# xv11_nucleo_shield.net
KiCad netlist of a schematic drawn in EAGLE
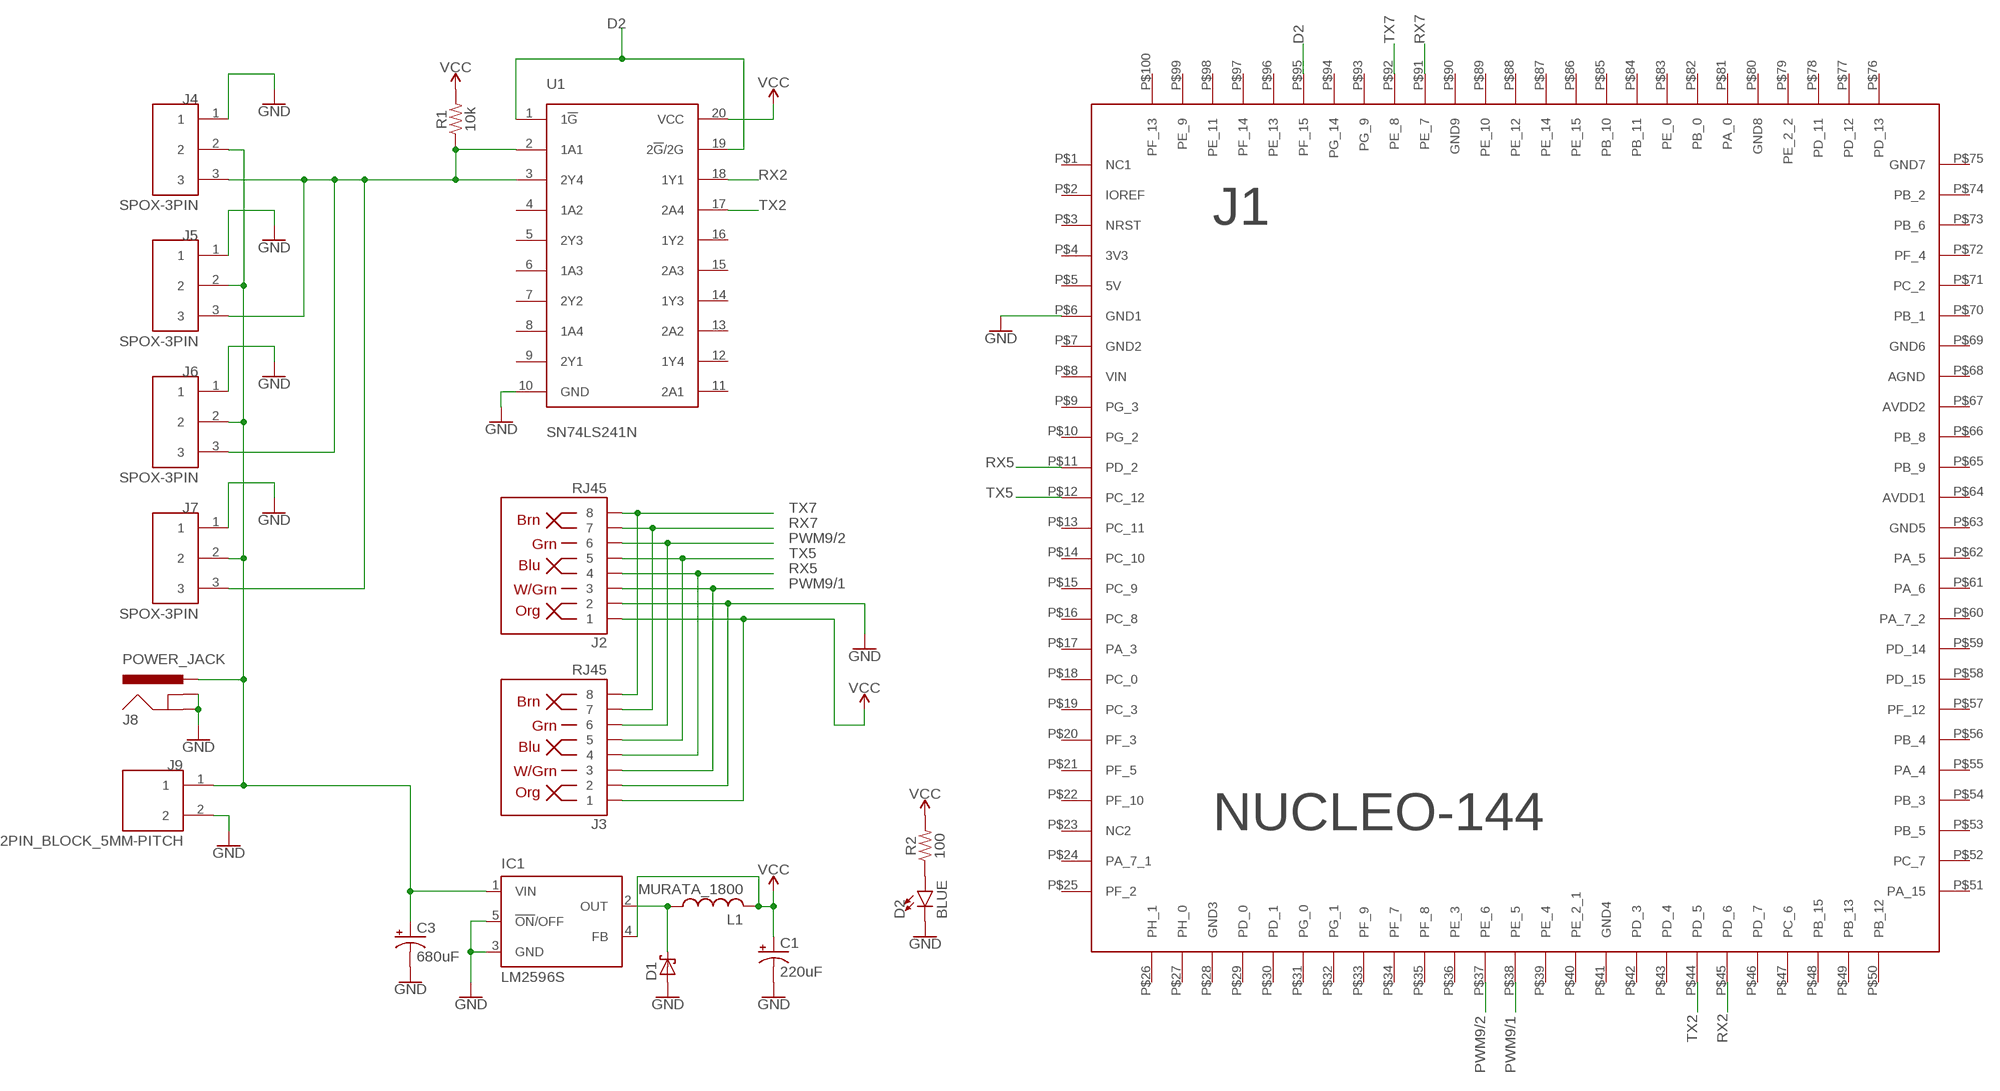
[diagram p0: schematic, sheet 1]

(export (version "E")
  (design (tool "Eeschema 10.0.6"))
  (components
    (comp (ref "C1")
      (value "220uF")
      (footprint "eagle-import:CPOL-RADIAL-2.5MM-6.5MM")
      (libsource (lib "eagle-import") (part "100UF-POLAR-RADIAL-2.5MM-25V-20%"))
    )
    (comp (ref "C3")
      (value "680uF")
      (footprint "eagle-import:EEU-FR1C681L")
      (libsource (lib "eagle-import") (part "EEU-FR1C681L"))
    )
    (comp (ref "D1")
      (value "SCHOTTKY-DIODEDO201T15")
      (footprint "eagle-import:DO201T15")
      (libsource (lib "eagle-import") (part "SCHOTTKY-DIODEDO201T15"))
    )
    (comp (ref "D2")
      (value "BLUE")
      (footprint "eagle-import:LED-1206")
      (libsource (lib "eagle-import") (part "LED-BLUE1206"))
    )
    (comp (ref "IC1")
      (value "LM2596S")
      (footprint "eagle-import:TO263-5")
      (fields (field (name "MF") "NATIONAL SEMICONDUCTOR") (field (name "MPN") "LM2596S-ADJ/NOPB"))
      (libsource (lib "eagle-import") (part "LM2596S"))
    )
    (comp (ref "J1")
      (value "NUCLEO-144")
      (footprint "eagle-import:NUCLEO-144")
      (libsource (lib "eagle-import") (part "NUCLEO-144"))
    )
    (comp (ref "J2")
      (value "RJ45")
      (footprint "eagle-import:RJ45-8")
      (libsource (lib "eagle-import") (part "RJ45-8"))
    )
    (comp (ref "J3")
      (value "RJ45")
      (footprint "eagle-import:RJ45-8")
      (libsource (lib "eagle-import") (part "RJ45-8"))
    )
    (comp (ref "J4")
      (value "SPOX-3PIN")
      (footprint "eagle-import:SPOX-3PIN")
      (libsource (lib "eagle-import") (part "SPOX-3PIN"))
    )
    (comp (ref "J5")
      (value "SPOX-3PIN")
      (footprint "eagle-import:SPOX-3PIN")
      (libsource (lib "eagle-import") (part "SPOX-3PIN"))
    )
    (comp (ref "J6")
      (value "SPOX-3PIN")
      (footprint "eagle-import:SPOX-3PIN")
      (libsource (lib "eagle-import") (part "SPOX-3PIN"))
    )
    (comp (ref "J7")
      (value "SPOX-3PIN")
      (footprint "eagle-import:SPOX-3PIN")
      (libsource (lib "eagle-import") (part "SPOX-3PIN"))
    )
    (comp (ref "J8")
      (value "POWER_JACK")
      (footprint "eagle-import:POWER_JACK_PTH")
      (libsource (lib "eagle-import") (part "POWER_JACK"))
    )
    (comp (ref "J9")
      (value "2PIN_BLOCK_5MM-PITCH")
      (footprint "eagle-import:2PIN_BLOCK_5MM-PITCH")
      (libsource (lib "eagle-import") (part "2PIN_BLOCK_5MM-PITCH"))
    )
    (comp (ref "L1")
      (value "MURATA_1800")
      (footprint "eagle-import:MURATA_1800")
      (libsource (lib "eagle-import") (part "MURATA_1800"))
    )
    (comp (ref "R1")
      (value "10k")
      (footprint "eagle-import:AXIAL-0.3")
      (libsource (lib "eagle-import") (part "10KOHM-HORIZ-1/4W-1%"))
    )
    (comp (ref "R2")
      (value "100")
      (footprint "eagle-import:AXIAL-0.3")
      (libsource (lib "eagle-import") (part "10KOHM-HORIZ-1/4W-1%"))
    )
    (comp (ref "U1")
      (value "SN74LS241N")
      (footprint "eagle-import:DIL20")
      (libsource (lib "eagle-import") (part "SN74LS241N"))
    )
  )
  (nets
    (net (code "1") (name "/D2") (class "Default")
      (node (ref "J1") (pin "P$95") (pinfunction "PF_15_P$95") (pintype "bidirectional"))
      (node (ref "U1") (pin "1") (pinfunction "1~{G}_1") (pintype "bidirectional"))
      (node (ref "U1") (pin "19") (pinfunction "2~{G}/2G_19") (pintype "bidirectional"))
    )
    (net (code "2") (name "/PWM9{slash}1") (class "Default")
      (node (ref "J1") (pin "P$38") (pinfunction "PE_5_P$38") (pintype "bidirectional"))
      (node (ref "J2") (pin "3") (pinfunction "3_3") (pintype "bidirectional"))
      (node (ref "J3") (pin "3") (pinfunction "3_3") (pintype "bidirectional"))
    )
    (net (code "3") (name "/PWM9{slash}2") (class "Default")
      (node (ref "J1") (pin "P$37") (pinfunction "PE_6_P$37") (pintype "bidirectional"))
      (node (ref "J2") (pin "6") (pinfunction "6_6") (pintype "bidirectional"))
      (node (ref "J3") (pin "6") (pinfunction "6_6") (pintype "bidirectional"))
    )
    (net (code "4") (name "/RX2") (class "Default")
      (node (ref "J1") (pin "P$45") (pinfunction "PD_6_P$45") (pintype "bidirectional"))
      (node (ref "U1") (pin "18") (pinfunction "1Y1_18") (pintype "bidirectional"))
    )
    (net (code "5") (name "/RX5") (class "Default")
      (node (ref "J1") (pin "P$11") (pinfunction "PD_2_P$11") (pintype "bidirectional"))
      (node (ref "J2") (pin "4") (pinfunction "4_4") (pintype "bidirectional"))
      (node (ref "J3") (pin "4") (pinfunction "4_4") (pintype "bidirectional"))
    )
    (net (code "6") (name "/RX7") (class "Default")
      (node (ref "J1") (pin "P$91") (pinfunction "PE_7_P$91") (pintype "bidirectional"))
      (node (ref "J2") (pin "7") (pinfunction "7_7") (pintype "bidirectional"))
      (node (ref "J3") (pin "7") (pinfunction "7_7") (pintype "bidirectional"))
    )
    (net (code "7") (name "/TX2") (class "Default")
      (node (ref "J1") (pin "P$44") (pinfunction "PD_5_P$44") (pintype "bidirectional"))
      (node (ref "U1") (pin "17") (pinfunction "2A4_17") (pintype "bidirectional"))
    )
    (net (code "8") (name "/TX5") (class "Default")
      (node (ref "J1") (pin "P$12") (pinfunction "PC_12_P$12") (pintype "bidirectional"))
      (node (ref "J2") (pin "5") (pinfunction "5_5") (pintype "bidirectional"))
      (node (ref "J3") (pin "5") (pinfunction "5_5") (pintype "bidirectional"))
    )
    (net (code "9") (name "/TX7") (class "Default")
      (node (ref "J1") (pin "P$92") (pinfunction "PE_8_P$92") (pintype "bidirectional"))
      (node (ref "J2") (pin "8") (pinfunction "8_8") (pintype "bidirectional"))
      (node (ref "J3") (pin "8") (pinfunction "8_8") (pintype "bidirectional"))
    )
    (net (code "10") (name "GND") (class "Default")
      (node (ref "C1") (pin "2") (pinfunction "-_2") (pintype "passive"))
      (node (ref "C3") (pin "P$2") (pinfunction "-_P$2") (pintype "passive"))
      (node (ref "D1") (pin "A") (pinfunction "A_A") (pintype "passive"))
      (node (ref "D2") (pin "C") (pinfunction "C_C") (pintype "passive"))
      (node (ref "IC1") (pin "3") (pinfunction "GND_3") (pintype "power_in"))
      (node (ref "IC1") (pin "5") (pinfunction "~{ON}/OFF_5") (pintype "input"))
      (node (ref "J1") (pin "P$6") (pinfunction "GND1_P$6") (pintype "bidirectional"))
      (node (ref "J2") (pin "2") (pinfunction "2_2") (pintype "bidirectional"))
      (node (ref "J3") (pin "2") (pinfunction "2_2") (pintype "bidirectional"))
      (node (ref "J4") (pin "1") (pinfunction "1_1") (pintype "bidirectional"))
      (node (ref "J5") (pin "1") (pinfunction "1_1") (pintype "bidirectional"))
      (node (ref "J6") (pin "1") (pinfunction "1_1") (pintype "bidirectional"))
      (node (ref "J7") (pin "1") (pinfunction "1_1") (pintype "bidirectional"))
      (node (ref "J8") (pin "GND") (pinfunction "GND_GND") (pintype "bidirectional"))
      (node (ref "J8") (pin "GNDBREAK") (pinfunction "GNDBREAK_GNDBREAK") (pintype "bidirectional"))
      (node (ref "J9") (pin "2") (pinfunction "2_2") (pintype "bidirectional"))
      (node (ref "U1") (pin "10") (pinfunction "GND_10") (pintype "bidirectional"))
    )
    (net (code "11") (name "Net-(C3-+)") (class "Default")
      (node (ref "C3") (pin "P$1") (pinfunction "+_P$1") (pintype "passive"))
      (node (ref "IC1") (pin "1") (pinfunction "VIN_1") (pintype "input"))
      (node (ref "J4") (pin "2") (pinfunction "2_2") (pintype "bidirectional"))
      (node (ref "J5") (pin "2") (pinfunction "2_2") (pintype "bidirectional"))
      (node (ref "J6") (pin "2") (pinfunction "2_2") (pintype "bidirectional"))
      (node (ref "J7") (pin "2") (pinfunction "2_2") (pintype "bidirectional"))
      (node (ref "J8") (pin "PWR") (pinfunction "PWR_PWR") (pintype "bidirectional"))
      (node (ref "J9") (pin "1") (pinfunction "1_1") (pintype "bidirectional"))
    )
    (net (code "12") (name "Net-(IC1-OUT)") (class "Default")
      (node (ref "D1") (pin "C") (pinfunction "C_C") (pintype "passive"))
      (node (ref "IC1") (pin "2") (pinfunction "OUT_2") (pintype "output"))
      (node (ref "L1") (pin "P$1") (pinfunction "1_P$1") (pintype "passive"))
    )
    (net (code "13") (name "Net-(R1-1)") (class "Default")
      (node (ref "J4") (pin "3") (pinfunction "3_3") (pintype "bidirectional"))
      (node (ref "J5") (pin "3") (pinfunction "3_3") (pintype "bidirectional"))
      (node (ref "J6") (pin "3") (pinfunction "3_3") (pintype "bidirectional"))
      (node (ref "J7") (pin "3") (pinfunction "3_3") (pintype "bidirectional"))
      (node (ref "R1") (pin "P$1") (pinfunction "1_P$1") (pintype "passive"))
      (node (ref "U1") (pin "2") (pinfunction "1A1_2") (pintype "bidirectional"))
      (node (ref "U1") (pin "3") (pinfunction "2Y4_3") (pintype "bidirectional"))
    )
    (net (code "14") (name "Net-(R2-1)") (class "Default")
      (node (ref "D2") (pin "A") (pinfunction "A_A") (pintype "passive"))
      (node (ref "R2") (pin "P$1") (pinfunction "1_P$1") (pintype "passive"))
    )
    (net (code "15") (name "VCC") (class "Default")
      (node (ref "C1") (pin "1") (pinfunction "+_1") (pintype "passive"))
      (node (ref "IC1") (pin "4") (pinfunction "FB_4") (pintype "input"))
      (node (ref "J2") (pin "1") (pinfunction "1_1") (pintype "bidirectional"))
      (node (ref "J3") (pin "1") (pinfunction "1_1") (pintype "bidirectional"))
      (node (ref "L1") (pin "P$2") (pinfunction "2_P$2") (pintype "passive"))
      (node (ref "R1") (pin "P$2") (pinfunction "2_P$2") (pintype "passive"))
      (node (ref "R2") (pin "P$2") (pinfunction "2_P$2") (pintype "passive"))
      (node (ref "U1") (pin "20") (pinfunction "VCC_20") (pintype "bidirectional"))
    )
    (net (code "16") (name "unconnected-(J1-3V3-PadP$4)") (class "Default")
      (node (ref "J1") (pin "P$4") (pinfunction "3V3_P$4") (pintype "bidirectional"))
    )
    (net (code "17") (name "unconnected-(J1-5V-PadP$5)") (class "Default")
      (node (ref "J1") (pin "P$5") (pinfunction "5V_P$5") (pintype "bidirectional"))
    )
    (net (code "18") (name "unconnected-(J1-AGND-PadP$68)") (class "Default")
      (node (ref "J1") (pin "P$68") (pinfunction "AGND_P$68") (pintype "bidirectional"))
    )
    (net (code "19") (name "unconnected-(J1-AVDD1-PadP$64)") (class "Default")
      (node (ref "J1") (pin "P$64") (pinfunction "AVDD1_P$64") (pintype "bidirectional"))
    )
    (net (code "20") (name "unconnected-(J1-AVDD2-PadP$67)") (class "Default")
      (node (ref "J1") (pin "P$67") (pinfunction "AVDD2_P$67") (pintype "bidirectional"))
    )
    (net (code "21") (name "unconnected-(J1-GND2-PadP$7)") (class "Default")
      (node (ref "J1") (pin "P$7") (pinfunction "GND2_P$7") (pintype "bidirectional"))
    )
    (net (code "22") (name "unconnected-(J1-GND3-PadP$28)") (class "Default")
      (node (ref "J1") (pin "P$28") (pinfunction "GND3_P$28") (pintype "bidirectional"))
    )
    (net (code "23") (name "unconnected-(J1-GND4-PadP$41)") (class "Default")
      (node (ref "J1") (pin "P$41") (pinfunction "GND4_P$41") (pintype "bidirectional"))
    )
    (net (code "24") (name "unconnected-(J1-GND5-PadP$63)") (class "Default")
      (node (ref "J1") (pin "P$63") (pinfunction "GND5_P$63") (pintype "bidirectional"))
    )
    (net (code "25") (name "unconnected-(J1-GND6-PadP$69)") (class "Default")
      (node (ref "J1") (pin "P$69") (pinfunction "GND6_P$69") (pintype "bidirectional"))
    )
    (net (code "26") (name "unconnected-(J1-GND7-PadP$75)") (class "Default")
      (node (ref "J1") (pin "P$75") (pinfunction "GND7_P$75") (pintype "bidirectional"))
    )
    (net (code "27") (name "unconnected-(J1-GND8-PadP$80)") (class "Default")
      (node (ref "J1") (pin "P$80") (pinfunction "GND8_P$80") (pintype "bidirectional"))
    )
    (net (code "28") (name "unconnected-(J1-GND9-PadP$90)") (class "Default")
      (node (ref "J1") (pin "P$90") (pinfunction "GND9_P$90") (pintype "bidirectional"))
    )
    (net (code "29") (name "unconnected-(J1-IOREF-PadP$2)") (class "Default")
      (node (ref "J1") (pin "P$2") (pinfunction "IOREF_P$2") (pintype "bidirectional"))
    )
    (net (code "30") (name "unconnected-(J1-NC1-PadP$1)") (class "Default")
      (node (ref "J1") (pin "P$1") (pinfunction "NC1_P$1") (pintype "bidirectional"))
    )
    (net (code "31") (name "unconnected-(J1-NC2-PadP$23)") (class "Default")
      (node (ref "J1") (pin "P$23") (pinfunction "NC2_P$23") (pintype "bidirectional"))
    )
    (net (code "32") (name "unconnected-(J1-NRST-PadP$3)") (class "Default")
      (node (ref "J1") (pin "P$3") (pinfunction "NRST_P$3") (pintype "bidirectional"))
    )
    (net (code "33") (name "unconnected-(J1-PA_0-PadP$81)") (class "Default")
      (node (ref "J1") (pin "P$81") (pinfunction "PA_0_P$81") (pintype "bidirectional"))
    )
    (net (code "34") (name "unconnected-(J1-PA_3-PadP$17)") (class "Default")
      (node (ref "J1") (pin "P$17") (pinfunction "PA_3_P$17") (pintype "bidirectional"))
    )
    (net (code "35") (name "unconnected-(J1-PA_4-PadP$55)") (class "Default")
      (node (ref "J1") (pin "P$55") (pinfunction "PA_4_P$55") (pintype "bidirectional"))
    )
    (net (code "36") (name "unconnected-(J1-PA_5-PadP$62)") (class "Default")
      (node (ref "J1") (pin "P$62") (pinfunction "PA_5_P$62") (pintype "bidirectional"))
    )
    (net (code "37") (name "unconnected-(J1-PA_6-PadP$61)") (class "Default")
      (node (ref "J1") (pin "P$61") (pinfunction "PA_6_P$61") (pintype "bidirectional"))
    )
    (net (code "38") (name "unconnected-(J1-PA_7_1-PadP$24)") (class "Default")
      (node (ref "J1") (pin "P$24") (pinfunction "PA_7_1_P$24") (pintype "bidirectional"))
    )
    (net (code "39") (name "unconnected-(J1-PA_7_2-PadP$60)") (class "Default")
      (node (ref "J1") (pin "P$60") (pinfunction "PA_7_2_P$60") (pintype "bidirectional"))
    )
    (net (code "40") (name "unconnected-(J1-PA_15-PadP$51)") (class "Default")
      (node (ref "J1") (pin "P$51") (pinfunction "PA_15_P$51") (pintype "bidirectional"))
    )
    (net (code "41") (name "unconnected-(J1-PB_0-PadP$82)") (class "Default")
      (node (ref "J1") (pin "P$82") (pinfunction "PB_0_P$82") (pintype "bidirectional"))
    )
    (net (code "42") (name "unconnected-(J1-PB_1-PadP$70)") (class "Default")
      (node (ref "J1") (pin "P$70") (pinfunction "PB_1_P$70") (pintype "bidirectional"))
    )
    (net (code "43") (name "unconnected-(J1-PB_2-PadP$74)") (class "Default")
      (node (ref "J1") (pin "P$74") (pinfunction "PB_2_P$74") (pintype "bidirectional"))
    )
    (net (code "44") (name "unconnected-(J1-PB_3-PadP$54)") (class "Default")
      (node (ref "J1") (pin "P$54") (pinfunction "PB_3_P$54") (pintype "bidirectional"))
    )
    (net (code "45") (name "unconnected-(J1-PB_4-PadP$56)") (class "Default")
      (node (ref "J1") (pin "P$56") (pinfunction "PB_4_P$56") (pintype "bidirectional"))
    )
    (net (code "46") (name "unconnected-(J1-PB_5-PadP$53)") (class "Default")
      (node (ref "J1") (pin "P$53") (pinfunction "PB_5_P$53") (pintype "bidirectional"))
    )
    (net (code "47") (name "unconnected-(J1-PB_6-PadP$73)") (class "Default")
      (node (ref "J1") (pin "P$73") (pinfunction "PB_6_P$73") (pintype "bidirectional"))
    )
    (net (code "48") (name "unconnected-(J1-PB_8-PadP$66)") (class "Default")
      (node (ref "J1") (pin "P$66") (pinfunction "PB_8_P$66") (pintype "bidirectional"))
    )
    (net (code "49") (name "unconnected-(J1-PB_9-PadP$65)") (class "Default")
      (node (ref "J1") (pin "P$65") (pinfunction "PB_9_P$65") (pintype "bidirectional"))
    )
    (net (code "50") (name "unconnected-(J1-PB_10-PadP$85)") (class "Default")
      (node (ref "J1") (pin "P$85") (pinfunction "PB_10_P$85") (pintype "bidirectional"))
    )
    (net (code "51") (name "unconnected-(J1-PB_11-PadP$84)") (class "Default")
      (node (ref "J1") (pin "P$84") (pinfunction "PB_11_P$84") (pintype "bidirectional"))
    )
    (net (code "52") (name "unconnected-(J1-PB_12-PadP$50)") (class "Default")
      (node (ref "J1") (pin "P$50") (pinfunction "PB_12_P$50") (pintype "bidirectional"))
    )
    (net (code "53") (name "unconnected-(J1-PB_13-PadP$49)") (class "Default")
      (node (ref "J1") (pin "P$49") (pinfunction "PB_13_P$49") (pintype "bidirectional"))
    )
    (net (code "54") (name "unconnected-(J1-PB_15-PadP$48)") (class "Default")
      (node (ref "J1") (pin "P$48") (pinfunction "PB_15_P$48") (pintype "bidirectional"))
    )
    (net (code "55") (name "unconnected-(J1-PC_0-PadP$18)") (class "Default")
      (node (ref "J1") (pin "P$18") (pinfunction "PC_0_P$18") (pintype "bidirectional"))
    )
    (net (code "56") (name "unconnected-(J1-PC_2-PadP$71)") (class "Default")
      (node (ref "J1") (pin "P$71") (pinfunction "PC_2_P$71") (pintype "bidirectional"))
    )
    (net (code "57") (name "unconnected-(J1-PC_3-PadP$19)") (class "Default")
      (node (ref "J1") (pin "P$19") (pinfunction "PC_3_P$19") (pintype "bidirectional"))
    )
    (net (code "58") (name "unconnected-(J1-PC_6-PadP$47)") (class "Default")
      (node (ref "J1") (pin "P$47") (pinfunction "PC_6_P$47") (pintype "bidirectional"))
    )
    (net (code "59") (name "unconnected-(J1-PC_7-PadP$52)") (class "Default")
      (node (ref "J1") (pin "P$52") (pinfunction "PC_7_P$52") (pintype "bidirectional"))
    )
    (net (code "60") (name "unconnected-(J1-PC_8-PadP$16)") (class "Default")
      (node (ref "J1") (pin "P$16") (pinfunction "PC_8_P$16") (pintype "bidirectional"))
    )
    (net (code "61") (name "unconnected-(J1-PC_9-PadP$15)") (class "Default")
      (node (ref "J1") (pin "P$15") (pinfunction "PC_9_P$15") (pintype "bidirectional"))
    )
    (net (code "62") (name "unconnected-(J1-PC_10-PadP$14)") (class "Default")
      (node (ref "J1") (pin "P$14") (pinfunction "PC_10_P$14") (pintype "bidirectional"))
    )
    (net (code "63") (name "unconnected-(J1-PC_11-PadP$13)") (class "Default")
      (node (ref "J1") (pin "P$13") (pinfunction "PC_11_P$13") (pintype "bidirectional"))
    )
    (net (code "64") (name "unconnected-(J1-PD_0-PadP$29)") (class "Default")
      (node (ref "J1") (pin "P$29") (pinfunction "PD_0_P$29") (pintype "bidirectional"))
    )
    (net (code "65") (name "unconnected-(J1-PD_1-PadP$30)") (class "Default")
      (node (ref "J1") (pin "P$30") (pinfunction "PD_1_P$30") (pintype "bidirectional"))
    )
    (net (code "66") (name "unconnected-(J1-PD_3-PadP$42)") (class "Default")
      (node (ref "J1") (pin "P$42") (pinfunction "PD_3_P$42") (pintype "bidirectional"))
    )
    (net (code "67") (name "unconnected-(J1-PD_4-PadP$43)") (class "Default")
      (node (ref "J1") (pin "P$43") (pinfunction "PD_4_P$43") (pintype "bidirectional"))
    )
    (net (code "68") (name "unconnected-(J1-PD_7-PadP$46)") (class "Default")
      (node (ref "J1") (pin "P$46") (pinfunction "PD_7_P$46") (pintype "bidirectional"))
    )
    (net (code "69") (name "unconnected-(J1-PD_11-PadP$78)") (class "Default")
      (node (ref "J1") (pin "P$78") (pinfunction "PD_11_P$78") (pintype "bidirectional"))
    )
    (net (code "70") (name "unconnected-(J1-PD_12-PadP$77)") (class "Default")
      (node (ref "J1") (pin "P$77") (pinfunction "PD_12_P$77") (pintype "bidirectional"))
    )
    (net (code "71") (name "unconnected-(J1-PD_13-PadP$76)") (class "Default")
      (node (ref "J1") (pin "P$76") (pinfunction "PD_13_P$76") (pintype "bidirectional"))
    )
    (net (code "72") (name "unconnected-(J1-PD_14-PadP$59)") (class "Default")
      (node (ref "J1") (pin "P$59") (pinfunction "PD_14_P$59") (pintype "bidirectional"))
    )
    (net (code "73") (name "unconnected-(J1-PD_15-PadP$58)") (class "Default")
      (node (ref "J1") (pin "P$58") (pinfunction "PD_15_P$58") (pintype "bidirectional"))
    )
    (net (code "74") (name "unconnected-(J1-PE_0-PadP$83)") (class "Default")
      (node (ref "J1") (pin "P$83") (pinfunction "PE_0_P$83") (pintype "bidirectional"))
    )
    (net (code "75") (name "unconnected-(J1-PE_2_1-PadP$40)") (class "Default")
      (node (ref "J1") (pin "P$40") (pinfunction "PE_2_1_P$40") (pintype "bidirectional"))
    )
    (net (code "76") (name "unconnected-(J1-PE_2_2-PadP$79)") (class "Default")
      (node (ref "J1") (pin "P$79") (pinfunction "PE_2_2_P$79") (pintype "bidirectional"))
    )
    (net (code "77") (name "unconnected-(J1-PE_3-PadP$36)") (class "Default")
      (node (ref "J1") (pin "P$36") (pinfunction "PE_3_P$36") (pintype "bidirectional"))
    )
    (net (code "78") (name "unconnected-(J1-PE_4-PadP$39)") (class "Default")
      (node (ref "J1") (pin "P$39") (pinfunction "PE_4_P$39") (pintype "bidirectional"))
    )
    (net (code "79") (name "unconnected-(J1-PE_9-PadP$99)") (class "Default")
      (node (ref "J1") (pin "P$99") (pinfunction "PE_9_P$99") (pintype "bidirectional"))
    )
    (net (code "80") (name "unconnected-(J1-PE_10-PadP$89)") (class "Default")
      (node (ref "J1") (pin "P$89") (pinfunction "PE_10_P$89") (pintype "bidirectional"))
    )
    (net (code "81") (name "unconnected-(J1-PE_11-PadP$98)") (class "Default")
      (node (ref "J1") (pin "P$98") (pinfunction "PE_11_P$98") (pintype "bidirectional"))
    )
    (net (code "82") (name "unconnected-(J1-PE_12-PadP$88)") (class "Default")
      (node (ref "J1") (pin "P$88") (pinfunction "PE_12_P$88") (pintype "bidirectional"))
    )
    (net (code "83") (name "unconnected-(J1-PE_13-PadP$96)") (class "Default")
      (node (ref "J1") (pin "P$96") (pinfunction "PE_13_P$96") (pintype "bidirectional"))
    )
    (net (code "84") (name "unconnected-(J1-PE_14-PadP$87)") (class "Default")
      (node (ref "J1") (pin "P$87") (pinfunction "PE_14_P$87") (pintype "bidirectional"))
    )
    (net (code "85") (name "unconnected-(J1-PE_15-PadP$86)") (class "Default")
      (node (ref "J1") (pin "P$86") (pinfunction "PE_15_P$86") (pintype "bidirectional"))
    )
    (net (code "86") (name "unconnected-(J1-PF_2-PadP$25)") (class "Default")
      (node (ref "J1") (pin "P$25") (pinfunction "PF_2_P$25") (pintype "bidirectional"))
    )
    (net (code "87") (name "unconnected-(J1-PF_3-PadP$20)") (class "Default")
      (node (ref "J1") (pin "P$20") (pinfunction "PF_3_P$20") (pintype "bidirectional"))
    )
    (net (code "88") (name "unconnected-(J1-PF_4-PadP$72)") (class "Default")
      (node (ref "J1") (pin "P$72") (pinfunction "PF_4_P$72") (pintype "bidirectional"))
    )
    (net (code "89") (name "unconnected-(J1-PF_5-PadP$21)") (class "Default")
      (node (ref "J1") (pin "P$21") (pinfunction "PF_5_P$21") (pintype "bidirectional"))
    )
    (net (code "90") (name "unconnected-(J1-PF_7-PadP$34)") (class "Default")
      (node (ref "J1") (pin "P$34") (pinfunction "PF_7_P$34") (pintype "bidirectional"))
    )
    (net (code "91") (name "unconnected-(J1-PF_8-PadP$35)") (class "Default")
      (node (ref "J1") (pin "P$35") (pinfunction "PF_8_P$35") (pintype "bidirectional"))
    )
    (net (code "92") (name "unconnected-(J1-PF_9-PadP$33)") (class "Default")
      (node (ref "J1") (pin "P$33") (pinfunction "PF_9_P$33") (pintype "bidirectional"))
    )
    (net (code "93") (name "unconnected-(J1-PF_10-PadP$22)") (class "Default")
      (node (ref "J1") (pin "P$22") (pinfunction "PF_10_P$22") (pintype "bidirectional"))
    )
    (net (code "94") (name "unconnected-(J1-PF_12-PadP$57)") (class "Default")
      (node (ref "J1") (pin "P$57") (pinfunction "PF_12_P$57") (pintype "bidirectional"))
    )
    (net (code "95") (name "unconnected-(J1-PF_13-PadP$100)") (class "Default")
      (node (ref "J1") (pin "P$100") (pinfunction "PF_13_P$100") (pintype "bidirectional"))
    )
    (net (code "96") (name "unconnected-(J1-PF_14-PadP$97)") (class "Default")
      (node (ref "J1") (pin "P$97") (pinfunction "PF_14_P$97") (pintype "bidirectional"))
    )
    (net (code "97") (name "unconnected-(J1-PG_0-PadP$31)") (class "Default")
      (node (ref "J1") (pin "P$31") (pinfunction "PG_0_P$31") (pintype "bidirectional"))
    )
    (net (code "98") (name "unconnected-(J1-PG_1-PadP$32)") (class "Default")
      (node (ref "J1") (pin "P$32") (pinfunction "PG_1_P$32") (pintype "bidirectional"))
    )
    (net (code "99") (name "unconnected-(J1-PG_2-PadP$10)") (class "Default")
      (node (ref "J1") (pin "P$10") (pinfunction "PG_2_P$10") (pintype "bidirectional"))
    )
    (net (code "100") (name "unconnected-(J1-PG_3-PadP$9)") (class "Default")
      (node (ref "J1") (pin "P$9") (pinfunction "PG_3_P$9") (pintype "bidirectional"))
    )
    (net (code "101") (name "unconnected-(J1-PG_9-PadP$93)") (class "Default")
      (node (ref "J1") (pin "P$93") (pinfunction "PG_9_P$93") (pintype "bidirectional"))
    )
    (net (code "102") (name "unconnected-(J1-PG_14-PadP$94)") (class "Default")
      (node (ref "J1") (pin "P$94") (pinfunction "PG_14_P$94") (pintype "bidirectional"))
    )
    (net (code "103") (name "unconnected-(J1-PH_0-PadP$27)") (class "Default")
      (node (ref "J1") (pin "P$27") (pinfunction "PH_0_P$27") (pintype "bidirectional"))
    )
    (net (code "104") (name "unconnected-(J1-PH_1-PadP$26)") (class "Default")
      (node (ref "J1") (pin "P$26") (pinfunction "PH_1_P$26") (pintype "bidirectional"))
    )
    (net (code "105") (name "unconnected-(J1-VIN-PadP$8)") (class "Default")
      (node (ref "J1") (pin "P$8") (pinfunction "VIN_P$8") (pintype "bidirectional"))
    )
    (net (code "106") (name "unconnected-(U1-1A2-Pad4)") (class "Default")
      (node (ref "U1") (pin "4") (pinfunction "1A2_4") (pintype "bidirectional"))
    )
    (net (code "107") (name "unconnected-(U1-1A3-Pad6)") (class "Default")
      (node (ref "U1") (pin "6") (pinfunction "1A3_6") (pintype "bidirectional"))
    )
    (net (code "108") (name "unconnected-(U1-1A4-Pad8)") (class "Default")
      (node (ref "U1") (pin "8") (pinfunction "1A4_8") (pintype "bidirectional"))
    )
    (net (code "109") (name "unconnected-(U1-1Y2-Pad16)") (class "Default")
      (node (ref "U1") (pin "16") (pinfunction "1Y2_16") (pintype "bidirectional"))
    )
    (net (code "110") (name "unconnected-(U1-1Y3-Pad14)") (class "Default")
      (node (ref "U1") (pin "14") (pinfunction "1Y3_14") (pintype "bidirectional"))
    )
    (net (code "111") (name "unconnected-(U1-1Y4-Pad12)") (class "Default")
      (node (ref "U1") (pin "12") (pinfunction "1Y4_12") (pintype "bidirectional"))
    )
    (net (code "112") (name "unconnected-(U1-2A1-Pad11)") (class "Default")
      (node (ref "U1") (pin "11") (pinfunction "2A1_11") (pintype "bidirectional"))
    )
    (net (code "113") (name "unconnected-(U1-2A2-Pad13)") (class "Default")
      (node (ref "U1") (pin "13") (pinfunction "2A2_13") (pintype "bidirectional"))
    )
    (net (code "114") (name "unconnected-(U1-2A3-Pad15)") (class "Default")
      (node (ref "U1") (pin "15") (pinfunction "2A3_15") (pintype "bidirectional"))
    )
    (net (code "115") (name "unconnected-(U1-2Y1-Pad9)") (class "Default")
      (node (ref "U1") (pin "9") (pinfunction "2Y1_9") (pintype "bidirectional"))
    )
    (net (code "116") (name "unconnected-(U1-2Y2-Pad7)") (class "Default")
      (node (ref "U1") (pin "7") (pinfunction "2Y2_7") (pintype "bidirectional"))
    )
    (net (code "117") (name "unconnected-(U1-2Y3-Pad5)") (class "Default")
      (node (ref "U1") (pin "5") (pinfunction "2Y3_5") (pintype "bidirectional"))
    )
  )
)
